# schematic.net
KiCad netlist of a schematic drawn in EAGLE
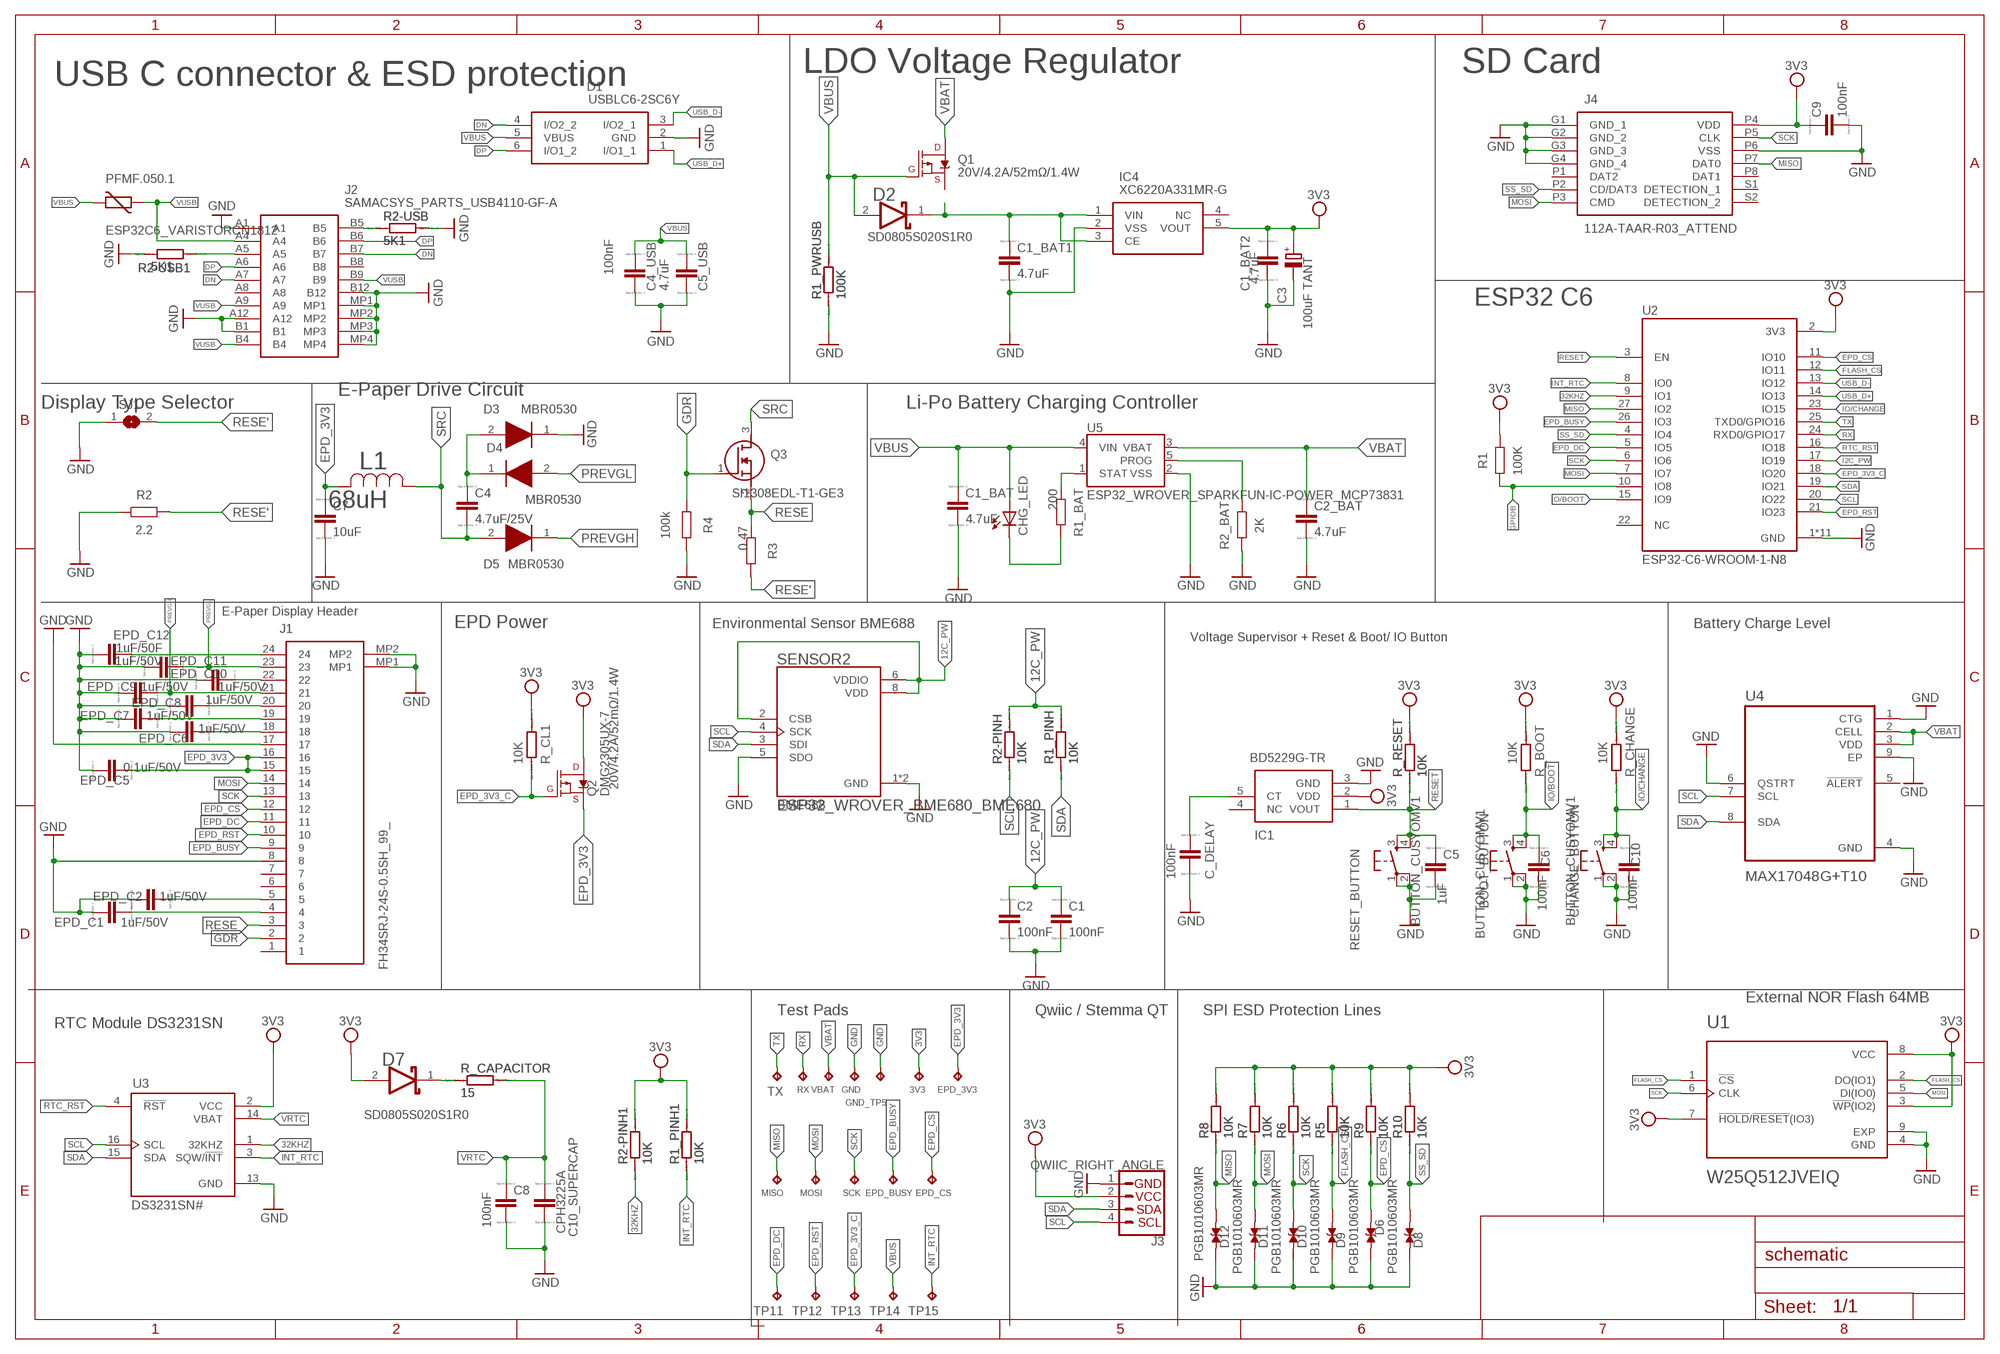
[diagram p0: schematic, sheet 1]

(export (version "E")
  (design (tool "Eeschema 10.0.6"))
  (components
    (comp (ref "3V3")
      (value "TPTP20R")
      (footprint "eagle-import:TP20R")
      (libsource (lib "eagle-import") (part "TPTP20R"))
    )
    (comp (ref "BOOT_BUTTON")
      (value "BUTTON_CUSYOMV1")
      (footprint "eagle-import:MYBUTTON")
      (libsource (lib "eagle-import") (part "BUTTON_CUSYOMV1"))
    )
    (comp (ref "C1")
      (value "100nF")
      (footprint "eagle-import:ESP32_WROVER_EAGLE-LTSPICE_C0402")
      (libsource (lib "eagle-import") (part "ESP32_WROVER_EAGLE-LTSPICE_CC0402"))
    )
    (comp (ref "C1_BAT")
      (value "4.7uF")
      (footprint "eagle-import:ESP32_WROVER_EAGLE-LTSPICE_C0402")
      (libsource (lib "eagle-import") (part "ESP32_WROVER_EAGLE-LTSPICE_CC0402"))
    )
    (comp (ref "C1_BAT1")
      (value "4.7uF")
      (footprint "eagle-import:ESP32_WROVER_EAGLE-LTSPICE_C0402")
      (libsource (lib "eagle-import") (part "ESP32_WROVER_EAGLE-LTSPICE_CC0402"))
    )
    (comp (ref "C1_BAT2")
      (value "4.7uF")
      (footprint "eagle-import:ESP32_WROVER_EAGLE-LTSPICE_C0402")
      (libsource (lib "eagle-import") (part "ESP32_WROVER_EAGLE-LTSPICE_CC0402"))
    )
    (comp (ref "C2")
      (value "100nF")
      (footprint "eagle-import:ESP32_WROVER_EAGLE-LTSPICE_C0402")
      (libsource (lib "eagle-import") (part "ESP32_WROVER_EAGLE-LTSPICE_CC0402"))
    )
    (comp (ref "C2_BAT")
      (value "4.7uF")
      (footprint "eagle-import:ESP32_WROVER_EAGLE-LTSPICE_C0402")
      (libsource (lib "eagle-import") (part "ESP32_WROVER_EAGLE-LTSPICE_CC0402"))
    )
    (comp (ref "C3")
      (value "100uF TANT")
      (footprint "eagle-import:RCL_CT3528")
      (libsource (lib "eagle-import") (part "RCL_CPOL-EUCT3528"))
    )
    (comp (ref "C4")
      (value "4.7uF/25V")
      (footprint "eagle-import:ESP32_WROVER_EAGLE-LTSPICE_C0402")
      (libsource (lib "eagle-import") (part "ESP32_WROVER_EAGLE-LTSPICE_CC0402"))
    )
    (comp (ref "C4_USB")
      (value "100nF")
      (footprint "eagle-import:ESP32_WROVER_EAGLE-LTSPICE_C0402")
      (libsource (lib "eagle-import") (part "ESP32_WROVER_EAGLE-LTSPICE_CC0402"))
    )
    (comp (ref "C5")
      (value "1uF")
      (footprint "eagle-import:EAGLE-LTSPICE_C0402")
      (libsource (lib "eagle-import") (part "EAGLE-LTSPICE_CC0402"))
    )
    (comp (ref "C5_USB")
      (value "4.7uF")
      (footprint "eagle-import:ESP32_WROVER_EAGLE-LTSPICE_C0402")
      (libsource (lib "eagle-import") (part "ESP32_WROVER_EAGLE-LTSPICE_CC0402"))
    )
    (comp (ref "C6")
      (value "100nF")
      (footprint "eagle-import:ESP32_WROVER_EAGLE-LTSPICE_C0402")
      (libsource (lib "eagle-import") (part "ESP32_WROVER_EAGLE-LTSPICE_CC0402"))
    )
    (comp (ref "C7")
      (value "10uF")
      (footprint "eagle-import:ESP32_WROVER_EAGLE-LTSPICE_C0402")
      (libsource (lib "eagle-import") (part "ESP32_WROVER_EAGLE-LTSPICE_CC0402"))
    )
    (comp (ref "C8")
      (value "100nF")
      (footprint "eagle-import:EAGLE-LTSPICE_C0402")
      (libsource (lib "eagle-import") (part "EAGLE-LTSPICE_CC0402"))
    )
    (comp (ref "C9")
      (value "100nF")
      (footprint "eagle-import:ESP32_WROVER_EAGLE-LTSPICE_C0402")
      (libsource (lib "eagle-import") (part "ESP32_WROVER_EAGLE-LTSPICE_CC0402"))
    )
    (comp (ref "C10")
      (value "100nF")
      (footprint "eagle-import:ESP32_WROVER_EAGLE-LTSPICE_C0402")
      (libsource (lib "eagle-import") (part "ESP32_WROVER_EAGLE-LTSPICE_CC0402"))
    )
    (comp (ref "C10_SUPERCAP")
      (value "CPH3225A")
      (footprint "eagle-import:EAGLE-LTSPICE_C0402")
      (libsource (lib "eagle-import") (part "EAGLE-LTSPICE_CC0402"))
    )
    (comp (ref "CHANGE_BUTTON")
      (value "BUTTON_CUSYOMV1")
      (footprint "eagle-import:MYBUTTON")
      (libsource (lib "eagle-import") (part "BUTTON_CUSYOMV1"))
    )
    (comp (ref "CHG_LED")
      (value "ADAFRUIT_LEDCHIP-LED0603")
      (footprint "eagle-import:ADAFRUIT_CHIP-LED0603")
      (libsource (lib "eagle-import") (part "ADAFRUIT_LEDCHIP-LED0603"))
    )
    (comp (ref "C_DELAY")
      (value "100nF")
      (footprint "eagle-import:ESP32_WROVER_EAGLE-LTSPICE_C0402")
      (libsource (lib "eagle-import") (part "ESP32_WROVER_EAGLE-LTSPICE_CC0402"))
    )
    (comp (ref "D1")
      (value "USBLC6-2SC6Y")
      (footprint "eagle-import:SOT95P280X145.0100-6N")
      (fields (field (name "MF") "STMicroelectronics"))
      (libsource (lib "eagle-import") (part "USBLC6-2SC6Y"))
    )
    (comp (ref "D2")
      (value "ESP32_WROVER_AVX---SD0805S020S1R0_AVX_SD0805S020S1R0_0_0AVX_SD0805S020S1R0_0_0")
      (footprint "eagle-import:ESP32_WROVER_AVX---SD0805S020S1R0_AVX_SD0805S020S1R0_0")
      (fields
        (field (name "DIGIKEY_PART_NUMBER") "478-7800-1-ND")
        (field (name "MF") "AVX")
        (field (name "MOUSER_PART_NUMBER") "581-SD0805S020S1R0")
      )
      (libsource (lib "eagle-import") (part "ESP32_WROVER_AVX---SD0805S020S1R0_AVX_SD0805S020S1R0_0_0AVX_SD0805S020S1R0_0_0"))
    )
    (comp (ref "D3")
      (value "MBR0530")
      (footprint "eagle-import:SOD3716X135.0100N")
      (fields (field (name "MF") "ON Semiconductor"))
      (libsource (lib "eagle-import") (part "MBR0530"))
    )
    (comp (ref "D4")
      (value "MBR0530")
      (footprint "eagle-import:SOD3716X135.0100N")
      (fields (field (name "MF") "ON Semiconductor"))
      (libsource (lib "eagle-import") (part "MBR0530"))
    )
    (comp (ref "D5")
      (value "MBR0530")
      (footprint "eagle-import:SOD3716X135.0100N")
      (fields (field (name "MF") "ON Semiconductor"))
      (libsource (lib "eagle-import") (part "MBR0530"))
    )
    (comp (ref "D6")
      (value "PGB1010603MR")
      (footprint "eagle-import:DIOC1608X36.0100N")
      (fields (field (name "MF") "Littelfuse Inc."))
      (libsource (lib "eagle-import") (part "PGB1010603MR"))
    )
    (comp (ref "D7")
      (value "ESP32_WROVER_AVX---SD0805S020S1R0_AVX_SD0805S020S1R0_0_0AVX_SD0805S020S1R0_0_0")
      (footprint "eagle-import:ESP32_WROVER_AVX---SD0805S020S1R0_AVX_SD0805S020S1R0_0")
      (fields
        (field (name "DIGIKEY_PART_NUMBER") "478-7800-1-ND")
        (field (name "MF") "AVX")
        (field (name "MOUSER_PART_NUMBER") "581-SD0805S020S1R0")
      )
      (libsource (lib "eagle-import") (part "ESP32_WROVER_AVX---SD0805S020S1R0_AVX_SD0805S020S1R0_0_0AVX_SD0805S020S1R0_0_0"))
    )
    (comp (ref "D8")
      (value "PGB1010603MR")
      (footprint "eagle-import:DIOC1608X36.0100N")
      (fields (field (name "MF") "Littelfuse Inc."))
      (libsource (lib "eagle-import") (part "PGB1010603MR"))
    )
    (comp (ref "D9")
      (value "PGB1010603MR")
      (footprint "eagle-import:DIOC1608X36.0100N")
      (fields (field (name "MF") "Littelfuse Inc."))
      (libsource (lib "eagle-import") (part "PGB1010603MR"))
    )
    (comp (ref "D10")
      (value "PGB1010603MR")
      (footprint "eagle-import:DIOC1608X36.0100N")
      (fields (field (name "MF") "Littelfuse Inc."))
      (libsource (lib "eagle-import") (part "PGB1010603MR"))
    )
    (comp (ref "D11")
      (value "PGB1010603MR")
      (footprint "eagle-import:DIOC1608X36.0100N")
      (fields (field (name "MF") "Littelfuse Inc."))
      (libsource (lib "eagle-import") (part "PGB1010603MR"))
    )
    (comp (ref "D12")
      (value "PGB1010603MR")
      (footprint "eagle-import:DIOC1608X36.0100N")
      (fields (field (name "MF") "Littelfuse Inc."))
      (libsource (lib "eagle-import") (part "PGB1010603MR"))
    )
    (comp (ref "EPD_3V3")
      (value "TPTP20R")
      (footprint "eagle-import:TP20R")
      (libsource (lib "eagle-import") (part "TPTP20R"))
    )
    (comp (ref "EPD_BUSY")
      (value "TPTP20R")
      (footprint "eagle-import:TP20R")
      (libsource (lib "eagle-import") (part "TPTP20R"))
    )
    (comp (ref "EPD_C1")
      (value "1uF/50V")
      (footprint "eagle-import:ESP32_WROVER_EAGLE-LTSPICE_C0402")
      (libsource (lib "eagle-import") (part "ESP32_WROVER_EAGLE-LTSPICE_CC0402"))
    )
    (comp (ref "EPD_C2")
      (value "1uF/50V")
      (footprint "eagle-import:ESP32_WROVER_EAGLE-LTSPICE_C0402")
      (libsource (lib "eagle-import") (part "ESP32_WROVER_EAGLE-LTSPICE_CC0402"))
    )
    (comp (ref "EPD_C5")
      (value "0.1uF/50V")
      (footprint "eagle-import:ESP32_WROVER_EAGLE-LTSPICE_C0402")
      (libsource (lib "eagle-import") (part "ESP32_WROVER_EAGLE-LTSPICE_CC0402"))
    )
    (comp (ref "EPD_C6")
      (value "1uF/50V")
      (footprint "eagle-import:ESP32_WROVER_EAGLE-LTSPICE_C0402")
      (libsource (lib "eagle-import") (part "ESP32_WROVER_EAGLE-LTSPICE_CC0402"))
    )
    (comp (ref "EPD_C7")
      (value "1uF/50V")
      (footprint "eagle-import:ESP32_WROVER_EAGLE-LTSPICE_C0402")
      (libsource (lib "eagle-import") (part "ESP32_WROVER_EAGLE-LTSPICE_CC0402"))
    )
    (comp (ref "EPD_C8")
      (value "1uF/50V")
      (footprint "eagle-import:ESP32_WROVER_EAGLE-LTSPICE_C0402")
      (libsource (lib "eagle-import") (part "ESP32_WROVER_EAGLE-LTSPICE_CC0402"))
    )
    (comp (ref "EPD_C9")
      (value "1uF/50V")
      (footprint "eagle-import:ESP32_WROVER_EAGLE-LTSPICE_C0402")
      (libsource (lib "eagle-import") (part "ESP32_WROVER_EAGLE-LTSPICE_CC0402"))
    )
    (comp (ref "EPD_C10")
      (value "1uF/50V")
      (footprint "eagle-import:ESP32_WROVER_EAGLE-LTSPICE_C0402")
      (libsource (lib "eagle-import") (part "ESP32_WROVER_EAGLE-LTSPICE_CC0402"))
    )
    (comp (ref "EPD_C11")
      (value "1uF/50V")
      (footprint "eagle-import:ESP32_WROVER_EAGLE-LTSPICE_C0402")
      (libsource (lib "eagle-import") (part "ESP32_WROVER_EAGLE-LTSPICE_CC0402"))
    )
    (comp (ref "EPD_C12")
      (value "1uF/50F")
      (footprint "eagle-import:ESP32_WROVER_EAGLE-LTSPICE_C0402")
      (libsource (lib "eagle-import") (part "ESP32_WROVER_EAGLE-LTSPICE_CC0402"))
    )
    (comp (ref "EPD_CS")
      (value "TPTP20R")
      (footprint "eagle-import:TP20R")
      (libsource (lib "eagle-import") (part "TPTP20R"))
    )
    (comp (ref "GND")
      (value "TPTP20R")
      (footprint "eagle-import:TP20R")
      (libsource (lib "eagle-import") (part "TPTP20R"))
    )
    (comp (ref "GND_TP5")
      (value "TPTP20R")
      (footprint "eagle-import:TP20R")
      (libsource (lib "eagle-import") (part "TPTP20R"))
    )
    (comp (ref "IC1")
      (value "BD5229G-TR")
      (footprint "eagle-import:SOT95P280X125.0100-5N")
      (fields (field (name "MOUSER_PART_NUMBER") "755-BD5229G-TR"))
      (libsource (lib "eagle-import") (part "BD5229G-TR"))
    )
    (comp (ref "IC4")
      (value "XC6220A331MR-G")
      (footprint "eagle-import:SOT95P280X120.0100-5N")
      (fields (field (name "MOUSER_PART_NUMBER") "865-XC6220A331MR-G"))
      (libsource (lib "eagle-import") (part "XC6220A331MR-G"))
    )
    (comp (ref "J1")
      (value "FH34SRJ-24S-0.5SH_99_")
      (footprint "eagle-import:FH34SRJ24S05SH99")
      (fields
        (field (name "MANUFACTURER_PART_NUMBER") "FH34SRJ-24S-0.5SH(99)")
        (field (name "MOUSER_PART_NUMBER") "798-FH34SRJ24S05SH99")
      )
      (libsource (lib "eagle-import") (part "FH34SRJ-24S-0.5SH_99_"))
    )
    (comp (ref "J2")
      (value "SAMACSYS_PARTS_USB4110-GF-A")
      (footprint "eagle-import:SAMACSYS_PARTS_USB4110GFA")
      (fields
        (field (name "MANUFACTURER_PART_NUMBER") "USB4110-GF-A")
        (field (name "MOUSER_PART_NUMBER") "640-USB4110-GF-A")
      )
      (libsource (lib "eagle-import") (part "SAMACSYS_PARTS_USB4110-GF-A"))
    )
    (comp (ref "J3")
      (value "QWIIC_RIGHT_ANGLE")
      (footprint "eagle-import:JST04_1MM_RA")
      (libsource (lib "eagle-import") (part "QWIIC_CONNECTORJS-1MM"))
    )
    (comp (ref "J4")
      (value "112A-TAAR-R03_ATTEND")
      (footprint "eagle-import:112ATAARR03ATTEND")
      (fields (field (name "MANUFACTURER_PART_NUMBER") "112A-TAAR-R03 ATTEND"))
      (libsource (lib "eagle-import") (part "112A-TAAR-R03_ATTEND"))
    )
    (comp (ref "L1")
      (value "68uH")
      (footprint "eagle-import:IND_4828-WE-TPC_WRE")
      (fields
        (field (name "MANUFACTURER_PART_NUMBER") "744043680")
        (field (name "COPYRIGHT") "Copyright (C) 2024 Ultra Librarian. All rights reserved.")
      )
      (libsource (lib "eagle-import") (part "744043680IND_4828-WE-TPC_WRE"))
    )
    (comp (ref "MISO")
      (value "TPTP20R")
      (footprint "eagle-import:TP20R")
      (libsource (lib "eagle-import") (part "TPTP20R"))
    )
    (comp (ref "MOSI")
      (value "TPTP20R")
      (footprint "eagle-import:TP20R")
      (libsource (lib "eagle-import") (part "TPTP20R"))
    )
    (comp (ref "PFMF.050.1")
      (value "ESP32C6_VARISTORCN1812")
      (footprint "eagle-import:ESP32C6_VARISTOR_CT_CN1812")
      (libsource (lib "eagle-import") (part "ESP32C6_VARISTORCN1812"))
    )
    (comp (ref "Q1")
      (value "20V/4.2A/52mΩ/1.4W")
      (footprint "eagle-import:ESP32_WROVER_SPARKFUN-DISCRETESEMI_SOT23-3")
      (libsource (lib "eagle-import") (part "ESP32_WROVER_SPARKFUN-DISCRETESEMI_MOSFET_PCH-DMG2305UX-7"))
    )
    (comp (ref "Q2")
      (value "20V/4.2A/52mΩ/1.4W")
      (footprint "eagle-import:ESP32_WROVER_SPARKFUN-DISCRETESEMI_SOT23-3")
      (libsource (lib "eagle-import") (part "ESP32_WROVER_SPARKFUN-DISCRETESEMI_MOSFET_PCH-DMG2305UX-7"))
    )
    (comp (ref "Q3")
      (value "SI1308EDL-T1-GE3")
      (footprint "eagle-import:SOT65P210X110.0100-3N")
      (fields (field (name "MF") "Vishay Siliconix"))
      (libsource (lib "eagle-import") (part "SI1308EDL-T1-GE3"))
    )
    (comp (ref "R1")
      (value "100K")
      (footprint "eagle-import:RESC1005X40.0100")
      (libsource (lib "eagle-import") (part "RCHIP-0402(1005-METRIC)_"))
    )
    (comp (ref "R1_BAT")
      (value "200")
      (footprint "eagle-import:RESC1005X40.0100")
      (libsource (lib "eagle-import") (part "RCHIP-0402(1005-METRIC)_"))
    )
    (comp (ref "R1_PINH")
      (value "10K")
      (footprint "eagle-import:ESP32_WROVER_EAGLE-LTSPICE_R0402")
      (libsource (lib "eagle-import") (part "ESP32_WROVER_EAGLE-LTSPICE_RR0402"))
    )
    (comp (ref "R1_PINH1")
      (value "10K")
      (footprint "eagle-import:ESP32_WROVER_EAGLE-LTSPICE_R0402")
      (libsource (lib "eagle-import") (part "ESP32_WROVER_EAGLE-LTSPICE_RR0402"))
    )
    (comp (ref "R1_PWRUSB")
      (value "100K")
      (footprint "eagle-import:ESP32_WROVER_EAGLE-LTSPICE_R0402")
      (libsource (lib "eagle-import") (part "ESP32_WROVER_EAGLE-LTSPICE_RR0402"))
    )
    (comp (ref "R2")
      (value "2.2")
      (footprint "eagle-import:RESC1005X40.0100")
      (libsource (lib "eagle-import") (part "RCHIP-0402(1005-METRIC)_"))
    )
    (comp (ref "R2-PINH")
      (value "10K")
      (footprint "eagle-import:ESP32_WROVER_EAGLE-LTSPICE_R0402")
      (libsource (lib "eagle-import") (part "ESP32_WROVER_EAGLE-LTSPICE_RR0402"))
    )
    (comp (ref "R2-PINH1")
      (value "10K")
      (footprint "eagle-import:ESP32_WROVER_EAGLE-LTSPICE_R0402")
      (libsource (lib "eagle-import") (part "ESP32_WROVER_EAGLE-LTSPICE_RR0402"))
    )
    (comp (ref "R2-USB")
      (value "5K1")
      (footprint "eagle-import:ESP32_WROVER_EAGLE-LTSPICE_R0402")
      (libsource (lib "eagle-import") (part "ESP32_WROVER_EAGLE-LTSPICE_RR0402"))
    )
    (comp (ref "R2-USB1")
      (value "5K1")
      (footprint "eagle-import:ESP32_WROVER_EAGLE-LTSPICE_R0402")
      (libsource (lib "eagle-import") (part "ESP32_WROVER_EAGLE-LTSPICE_RR0402"))
    )
    (comp (ref "R2_BAT")
      (value "2K")
      (footprint "eagle-import:RESC1005X40.0100")
      (libsource (lib "eagle-import") (part "RCHIP-0402(1005-METRIC)_"))
    )
    (comp (ref "R3")
      (value "0.47")
      (footprint "eagle-import:RESC1005X40.0100")
      (libsource (lib "eagle-import") (part "RCHIP-0402(1005-METRIC)_"))
    )
    (comp (ref "R4")
      (value "100k")
      (footprint "eagle-import:RESC1005X40.0100")
      (libsource (lib "eagle-import") (part "RCHIP-0402(1005-METRIC)_"))
    )
    (comp (ref "R5")
      (value "10K")
      (footprint "eagle-import:ESP32_WROVER_EAGLE-LTSPICE_R0402")
      (libsource (lib "eagle-import") (part "ESP32_WROVER_EAGLE-LTSPICE_RR0402"))
    )
    (comp (ref "R6")
      (value "10K")
      (footprint "eagle-import:ESP32_WROVER_EAGLE-LTSPICE_R0402")
      (libsource (lib "eagle-import") (part "ESP32_WROVER_EAGLE-LTSPICE_RR0402"))
    )
    (comp (ref "R7")
      (value "10K")
      (footprint "eagle-import:ESP32_WROVER_EAGLE-LTSPICE_R0402")
      (libsource (lib "eagle-import") (part "ESP32_WROVER_EAGLE-LTSPICE_RR0402"))
    )
    (comp (ref "R8")
      (value "10K")
      (footprint "eagle-import:ESP32_WROVER_EAGLE-LTSPICE_R0402")
      (libsource (lib "eagle-import") (part "ESP32_WROVER_EAGLE-LTSPICE_RR0402"))
    )
    (comp (ref "R9")
      (value "10K")
      (footprint "eagle-import:ESP32_WROVER_EAGLE-LTSPICE_R0402")
      (libsource (lib "eagle-import") (part "ESP32_WROVER_EAGLE-LTSPICE_RR0402"))
    )
    (comp (ref "R10")
      (value "10K")
      (footprint "eagle-import:ESP32_WROVER_EAGLE-LTSPICE_R0402")
      (libsource (lib "eagle-import") (part "ESP32_WROVER_EAGLE-LTSPICE_RR0402"))
    )
    (comp (ref "RESET_BUTTON")
      (value "BUTTON_CUSYOMV1")
      (footprint "eagle-import:MYBUTTON")
      (libsource (lib "eagle-import") (part "BUTTON_CUSYOMV1"))
    )
    (comp (ref "RX")
      (value "TPTP20R")
      (footprint "eagle-import:TP20R")
      (libsource (lib "eagle-import") (part "TPTP20R"))
    )
    (comp (ref "R_BOOT")
      (value "10K")
      (footprint "eagle-import:ESP32_WROVER_EAGLE-LTSPICE_R0402")
      (libsource (lib "eagle-import") (part "ESP32_WROVER_EAGLE-LTSPICE_RR0402"))
    )
    (comp (ref "R_CAPACITOR")
      (value "15")
      (footprint "eagle-import:ESP32_WROVER_EAGLE-LTSPICE_R0402")
      (libsource (lib "eagle-import") (part "ESP32_WROVER_EAGLE-LTSPICE_RR0402"))
    )
    (comp (ref "R_CHANGE")
      (value "10K")
      (footprint "eagle-import:ESP32_WROVER_EAGLE-LTSPICE_R0402")
      (libsource (lib "eagle-import") (part "ESP32_WROVER_EAGLE-LTSPICE_RR0402"))
    )
    (comp (ref "R_CL1")
      (value "10K")
      (footprint "eagle-import:ESP32_WROVER_EAGLE-LTSPICE_R0402")
      (libsource (lib "eagle-import") (part "ESP32_WROVER_EAGLE-LTSPICE_RR0402"))
    )
    (comp (ref "R_RESET")
      (value "10K")
      (footprint "eagle-import:ESP32_WROVER_EAGLE-LTSPICE_R0402")
      (libsource (lib "eagle-import") (part "ESP32_WROVER_EAGLE-LTSPICE_RR0402"))
    )
    (comp (ref "SCK")
      (value "TPTP20R")
      (footprint "eagle-import:TP20R")
      (libsource (lib "eagle-import") (part "TPTP20R"))
    )
    (comp (ref "SENSOR2")
      (value "ESP32_WROVER_BME680_BME680")
      (footprint "eagle-import:ESP32_WROVER_BME680_PSON80P300X300.0100X100-8N")
      (fields (field (name "MF") "Bosch Sensortec") (field (name "MP") "BME680"))
      (libsource (lib "eagle-import") (part "ESP32_WROVER_BME680_BME680"))
    )
    (comp (ref "SJ1") (value "SJ") (footprint "eagle-import:SJ") (libsource (lib "eagle-import") (part "SJ")))
    (comp (ref "TP11")
      (value "TPTP20R")
      (footprint "eagle-import:TP20R")
      (libsource (lib "eagle-import") (part "TPTP20R"))
    )
    (comp (ref "TP12")
      (value "TPTP20R")
      (footprint "eagle-import:TP20R")
      (libsource (lib "eagle-import") (part "TPTP20R"))
    )
    (comp (ref "TP13")
      (value "TPTP20R")
      (footprint "eagle-import:TP20R")
      (libsource (lib "eagle-import") (part "TPTP20R"))
    )
    (comp (ref "TP14")
      (value "TPTP20R")
      (footprint "eagle-import:TP20R")
      (libsource (lib "eagle-import") (part "TPTP20R"))
    )
    (comp (ref "TP15")
      (value "TPTP20R")
      (footprint "eagle-import:TP20R")
      (libsource (lib "eagle-import") (part "TPTP20R"))
    )
    (comp (ref "TX")
      (value "TPTP20R")
      (footprint "eagle-import:TP20R")
      (libsource (lib "eagle-import") (part "TPTP20R"))
    )
    (comp (ref "U1")
      (value "W25Q512JVEIQ")
      (footprint "eagle-import:SON127P600X800.0100X80-9N")
      (fields (field (name "MF") "Winbond Electronics"))
      (libsource (lib "eagle-import") (part "W25Q512JVEIQ"))
    )
    (comp (ref "U2")
      (value "ESP32-C6-WROOM-1-N8")
      (footprint "eagle-import:XCVR_ESP32-C6-WROOM-1-N8")
      (fields (field (name "MF") "Espressif Systems"))
      (libsource (lib "eagle-import") (part "ESP32-C6-WROOM-1-N8"))
    )
    (comp (ref "U3")
      (value "DS3231SN#")
      (footprint "eagle-import:SOIC127P1032X265.0100-16N")
      (fields (field (name "MF") "Analog Devices"))
      (libsource (lib "eagle-import") (part "DS3231SN#"))
    )
    (comp (ref "U4")
      (value "MAX17048G+T10")
      (footprint "eagle-import:SON50P200X200.0100X80-9N")
      (fields (field (name "MF") "Analog Devices") (field (name "MP") "MAX17048.0100G+T10"))
      (libsource (lib "eagle-import") (part "MAX17048.0100G+T10"))
    )
    (comp (ref "U5")
      (value "ESP32_WROVER_SPARKFUN-IC-POWER_MCP73831")
      (footprint "eagle-import:ESP32_WROVER_SPARKFUN-IC-POWER_SOT23-5")
      (libsource (lib "eagle-import") (part "ESP32_WROVER_SPARKFUN-IC-POWER_MCP73831"))
    )
    (comp (ref "VBAT")
      (value "TPTP20R")
      (footprint "eagle-import:TP20R")
      (libsource (lib "eagle-import") (part "TPTP20R"))
    )
  )
  (nets
    (net (code "1") (name "3V3") (class "Default")
      (node (ref "3V3") (pin "TP") (pinfunction "TP_TP") (pintype "input"))
      (node (ref "C1_BAT2") (pin "1") (pinfunction "1_1") (pintype "passive"))
      (node (ref "C3") (pin "+") (pinfunction "+_+") (pintype "passive"))
      (node (ref "C9") (pin "1") (pinfunction "1_1") (pintype "passive"))
      (node (ref "D7") (pin "2") (pinfunction "ANODE_2") (pintype "bidirectional"))
      (node (ref "IC1") (pin "2") (pinfunction "VDD_2") (pintype "bidirectional"))
      (node (ref "IC4") (pin "5") (pinfunction "VOUT_5") (pintype "bidirectional"))
      (node (ref "J3") (pin "2") (pinfunction "2_2") (pintype "power_in"))
      (node (ref "J4") (pin "P4") (pinfunction "VDD_P4") (pintype "bidirectional"))
      (node (ref "Q2") (pin "3") (pinfunction "D_3") (pintype "bidirectional"))
      (node (ref "R1") (pin "2") (pinfunction "2_2") (pintype "passive"))
      (node (ref "R10") (pin "2") (pinfunction "2_2") (pintype "passive"))
      (node (ref "R1_PINH1") (pin "2") (pinfunction "2_2") (pintype "passive"))
      (node (ref "R2-PINH1") (pin "2") (pinfunction "2_2") (pintype "passive"))
      (node (ref "R5") (pin "2") (pinfunction "2_2") (pintype "passive"))
      (node (ref "R6") (pin "2") (pinfunction "2_2") (pintype "passive"))
      (node (ref "R7") (pin "2") (pinfunction "2_2") (pintype "passive"))
      (node (ref "R8") (pin "2") (pinfunction "2_2") (pintype "passive"))
      (node (ref "R9") (pin "2") (pinfunction "2_2") (pintype "passive"))
      (node (ref "R_BOOT") (pin "2") (pinfunction "2_2") (pintype "passive"))
      (node (ref "R_CHANGE") (pin "2") (pinfunction "2_2") (pintype "passive"))
      (node (ref "R_CL1") (pin "2") (pinfunction "2_2") (pintype "passive"))
      (node (ref "R_RESET") (pin "2") (pinfunction "2_2") (pintype "passive"))
      (node (ref "U1") (pin "3") (pinfunction "~{WP}(IO2)_3") (pintype "bidirectional"))
      (node (ref "U1") (pin "7") (pinfunction "~{HOLD}/~{RESET}(IO3)_7") (pintype "bidirectional"))
      (node (ref "U1") (pin "8") (pinfunction "VCC_8") (pintype "power_in"))
      (node (ref "U2") (pin "2") (pinfunction "3V3_2") (pintype "power_in"))
      (node (ref "U3") (pin "2") (pinfunction "VCC_2") (pintype "power_in"))
    )
    (net (code "2") (name "12C_PW") (class "Default")
      (node (ref "C1") (pin "1") (pinfunction "1_1") (pintype "passive"))
      (node (ref "C2") (pin "1") (pinfunction "1_1") (pintype "passive"))
      (node (ref "R1_PINH") (pin "2") (pinfunction "2_2") (pintype "passive"))
      (node (ref "R2-PINH") (pin "2") (pinfunction "2_2") (pintype "passive"))
      (node (ref "SENSOR2") (pin "2") (pinfunction "CSB_2") (pintype "input"))
      (node (ref "SENSOR2") (pin "6") (pinfunction "VDDIO_6") (pintype "power_in"))
      (node (ref "SENSOR2") (pin "8") (pinfunction "VDD_8") (pintype "power_in"))
    )
    (net (code "3") (name "32KHZ") (class "Default")
      (node (ref "R2-PINH1") (pin "1") (pinfunction "1_1") (pintype "passive"))
      (node (ref "U2") (pin "9") (pinfunction "IO1_9") (pintype "bidirectional"))
      (node (ref "U3") (pin "1") (pinfunction "32KHZ_1") (pintype "output"))
    )
    (net (code "4") (name "DN") (class "Default")
      (node (ref "D1") (pin "4") (pinfunction "I/O2_2_4") (pintype "bidirectional"))
      (node (ref "J2") (pin "A7") (pinfunction "A7_A7") (pintype "bidirectional"))
      (node (ref "J2") (pin "B7") (pinfunction "B7_B7") (pintype "bidirectional"))
    )
    (net (code "5") (name "DP") (class "Default")
      (node (ref "D1") (pin "6") (pinfunction "I/O1_2_6") (pintype "bidirectional"))
      (node (ref "J2") (pin "A6") (pinfunction "A6_A6") (pintype "bidirectional"))
      (node (ref "J2") (pin "B6") (pinfunction "B6_B6") (pintype "bidirectional"))
    )
    (net (code "6") (name "EPD_3V3") (class "Default")
      (node (ref "C7") (pin "1") (pinfunction "1_1") (pintype "passive"))
      (node (ref "EPD_3V3") (pin "TP") (pinfunction "TP_TP") (pintype "input"))
      (node (ref "EPD_C5") (pin "2") (pinfunction "2_2") (pintype "passive"))
      (node (ref "J1") (pin "15") (pinfunction "15_15") (pintype "bidirectional"))
      (node (ref "J1") (pin "16") (pinfunction "16_16") (pintype "bidirectional"))
      (node (ref "L1") (pin "2") (pinfunction "2_2") (pintype "passive"))
      (node (ref "Q2") (pin "2") (pinfunction "S_2") (pintype "bidirectional"))
    )
    (net (code "7") (name "EPD_3V3_C") (class "Default")
      (node (ref "Q2") (pin "1") (pinfunction "G_1") (pintype "bidirectional"))
      (node (ref "R_CL1") (pin "1") (pinfunction "1_1") (pintype "passive"))
      (node (ref "TP13") (pin "TP") (pinfunction "TP_TP") (pintype "input"))
      (node (ref "U2") (pin "18") (pinfunction "IO20_18") (pintype "bidirectional"))
    )
    (net (code "8") (name "EPD_BUSY") (class "Default")
      (node (ref "EPD_BUSY") (pin "TP") (pinfunction "TP_TP") (pintype "input"))
      (node (ref "J1") (pin "9") (pinfunction "9_9") (pintype "bidirectional"))
      (node (ref "U2") (pin "26") (pinfunction "IO3_26") (pintype "bidirectional"))
    )
    (net (code "9") (name "EPD_CS") (class "Default")
      (node (ref "D6") (pin "2") (pinfunction "2_2") (pintype "passive"))
      (node (ref "EPD_CS") (pin "TP") (pinfunction "TP_TP") (pintype "input"))
      (node (ref "J1") (pin "12") (pinfunction "12_12") (pintype "bidirectional"))
      (node (ref "R9") (pin "1") (pinfunction "1_1") (pintype "passive"))
      (node (ref "U2") (pin "11") (pinfunction "IO10_11") (pintype "bidirectional"))
    )
    (net (code "10") (name "EPD_DC") (class "Default")
      (node (ref "J1") (pin "11") (pinfunction "11_11") (pintype "bidirectional"))
      (node (ref "TP11") (pin "TP") (pinfunction "TP_TP") (pintype "input"))
      (node (ref "U2") (pin "5") (pinfunction "IO5_5") (pintype "bidirectional"))
    )
    (net (code "11") (name "EPD_RST") (class "Default")
      (node (ref "J1") (pin "10") (pinfunction "10_10") (pintype "bidirectional"))
      (node (ref "TP12") (pin "TP") (pinfunction "TP_TP") (pintype "input"))
      (node (ref "U2") (pin "21") (pinfunction "IO23_21") (pintype "bidirectional"))
    )
    (net (code "12") (name "FLASH_CS") (class "Default")
      (node (ref "D9") (pin "2") (pinfunction "2_2") (pintype "passive"))
      (node (ref "R5") (pin "1") (pinfunction "1_1") (pintype "passive"))
      (node (ref "U1") (pin "1") (pinfunction "~{CS}_1") (pintype "input"))
      (node (ref "U2") (pin "12") (pinfunction "IO11_12") (pintype "bidirectional"))
    )
    (net (code "13") (name "GDR") (class "Default")
      (node (ref "J1") (pin "2") (pinfunction "2_2") (pintype "bidirectional"))
      (node (ref "Q3") (pin "1") (pinfunction "G_1") (pintype "bidirectional"))
      (node (ref "R4") (pin "2") (pinfunction "2_2") (pintype "passive"))
    )
    (net (code "14") (name "GND") (class "Default")
      (node (ref "BOOT_BUTTON") (pin "1") (pinfunction "1_1") (pintype "passive"))
      (node (ref "BOOT_BUTTON") (pin "2") (pinfunction "2_2") (pintype "passive"))
      (node (ref "C1") (pin "2") (pinfunction "2_2") (pintype "passive"))
      (node (ref "C10") (pin "2") (pinfunction "2_2") (pintype "passive"))
      (node (ref "C10_SUPERCAP") (pin "2") (pinfunction "2_2") (pintype "passive"))
      (node (ref "C1_BAT") (pin "2") (pinfunction "2_2") (pintype "passive"))
      (node (ref "C1_BAT1") (pin "2") (pinfunction "2_2") (pintype "passive"))
      (node (ref "C1_BAT2") (pin "2") (pinfunction "2_2") (pintype "passive"))
      (node (ref "C2") (pin "2") (pinfunction "2_2") (pintype "passive"))
      (node (ref "C2_BAT") (pin "2") (pinfunction "2_2") (pintype "passive"))
      (node (ref "C3") (pin "-") (pinfunction "-_-") (pintype "passive"))
      (node (ref "C4_USB") (pin "2") (pinfunction "2_2") (pintype "passive"))
      (node (ref "C5") (pin "2") (pinfunction "2_2") (pintype "passive"))
      (node (ref "C5_USB") (pin "2") (pinfunction "2_2") (pintype "passive"))
      (node (ref "C6") (pin "2") (pinfunction "2_2") (pintype "passive"))
      (node (ref "C7") (pin "2") (pinfunction "2_2") (pintype "passive"))
      (node (ref "C8") (pin "2") (pinfunction "2_2") (pintype "passive"))
      (node (ref "C9") (pin "2") (pinfunction "2_2") (pintype "passive"))
      (node (ref "CHANGE_BUTTON") (pin "1") (pinfunction "1_1") (pintype "passive"))
      (node (ref "CHANGE_BUTTON") (pin "2") (pinfunction "2_2") (pintype "passive"))
      (node (ref "C_DELAY") (pin "2") (pinfunction "2_2") (pintype "passive"))
      (node (ref "D1") (pin "2") (pinfunction "GND_2") (pintype "bidirectional"))
      (node (ref "D10") (pin "1") (pinfunction "1_1") (pintype "passive"))
      (node (ref "D11") (pin "1") (pinfunction "1_1") (pintype "passive"))
      (node (ref "D12") (pin "1") (pinfunction "1_1") (pintype "passive"))
      (node (ref "D3") (pin "1") (pinfunction "K_1") (pintype "bidirectional"))
      (node (ref "D6") (pin "1") (pinfunction "1_1") (pintype "passive"))
      (node (ref "D8") (pin "1") (pinfunction "1_1") (pintype "passive"))
      (node (ref "D9") (pin "1") (pinfunction "1_1") (pintype "passive"))
      (node (ref "EPD_C1") (pin "1") (pinfunction "1_1") (pintype "passive"))
      (node (ref "EPD_C10") (pin "1") (pinfunction "1_1") (pintype "passive"))
      (node (ref "EPD_C11") (pin "1") (pinfunction "1_1") (pintype "passive"))
      (node (ref "EPD_C12") (pin "1") (pinfunction "1_1") (pintype "passive"))
      (node (ref "EPD_C2") (pin "1") (pinfunction "1_1") (pintype "passive"))
      (node (ref "EPD_C5") (pin "1") (pinfunction "1_1") (pintype "passive"))
      (node (ref "EPD_C6") (pin "1") (pinfunction "1_1") (pintype "passive"))
      (node (ref "EPD_C7") (pin "1") (pinfunction "1_1") (pintype "passive"))
      (node (ref "EPD_C8") (pin "1") (pinfunction "1_1") (pintype "passive"))
      (node (ref "EPD_C9") (pin "1") (pinfunction "1_1") (pintype "passive"))
      (node (ref "GND") (pin "TP") (pinfunction "TP_TP") (pintype "input"))
      (node (ref "GND_TP5") (pin "TP") (pinfunction "TP_TP") (pintype "input"))
      (node (ref "IC1") (pin "3") (pinfunction "GND_3") (pintype "bidirectional"))
      (node (ref "IC4") (pin "2") (pinfunction "VSS_2") (pintype "bidirectional"))
      (node (ref "J1") (pin "17") (pinfunction "17_17") (pintype "bidirectional"))
      (node (ref "J1") (pin "8") (pinfunction "8_8") (pintype "bidirectional"))
      (node (ref "J1") (pin "MP1") (pinfunction "MP1_MP1") (pintype "bidirectional"))
      (node (ref "J1") (pin "MP2") (pinfunction "MP2_MP2") (pintype "bidirectional"))
      (node (ref "J2") (pin "A1") (pinfunction "A1_A1") (pintype "bidirectional"))
      (node (ref "J2") (pin "A12") (pinfunction "A12_A12") (pintype "bidirectional"))
      (node (ref "J2") (pin "B1") (pinfunction "B1_B1") (pintype "bidirectional"))
      (node (ref "J2") (pin "B12") (pinfunction "B12_B12") (pintype "bidirectional"))
      (node (ref "J2") (pin "MP1") (pinfunction "MP1_MP1") (pintype "bidirectional"))
      (node (ref "J2") (pin "MP2") (pinfunction "MP2_MP2") (pintype "bidirectional"))
      (node (ref "J2") (pin "MP3") (pinfunction "MP3_MP3") (pintype "bidirectional"))
      (node (ref "J2") (pin "MP4") (pinfunction "MP4_MP4") (pintype "bidirectional"))
      (node (ref "J3") (pin "1") (pinfunction "1_1") (pintype "power_in"))
      (node (ref "J4") (pin "G1") (pinfunction "GND_1_G1") (pintype "bidirectional"))
      (node (ref "J4") (pin "G2") (pinfunction "GND_2_G2") (pintype "bidirectional"))
      (node (ref "J4") (pin "G3") (pinfunction "GND_3_G3") (pintype "bidirectional"))
      (node (ref "J4") (pin "G4") (pinfunction "GND_4_G4") (pintype "bidirectional"))
      (node (ref "J4") (pin "P6") (pinfunction "VSS_P6") (pintype "bidirectional"))
      (node (ref "R1_PWRUSB") (pin "1") (pinfunction "1_1") (pintype "passive"))
      (node (ref "R2") (pin "1") (pinfunction "1_1") (pintype "passive"))
      (node (ref "R2-USB") (pin "2") (pinfunction "2_2") (pintype "passive"))
      (node (ref "R2-USB1") (pin "1") (pinfunction "1_1") (pintype "passive"))
      (node (ref "R2_BAT") (pin "1") (pinfunction "1_1") (pintype "passive"))
      (node (ref "R4") (pin "1") (pinfunction "1_1") (pintype "passive"))
      (node (ref "RESET_BUTTON") (pin "1") (pinfunction "1_1") (pintype "passive"))
      (node (ref "RESET_BUTTON") (pin "2") (pinfunction "2_2") (pintype "passive"))
      (node (ref "SENSOR2") (pin "1") (pinfunction "GND_1") (pintype "power_in"))
      (node (ref "SENSOR2") (pin "5") (pinfunction "SDO_5") (pintype "bidirectional"))
      (node (ref "SENSOR2") (pin "7") (pinfunction "GND_7") (pintype "power_in"))
      (node (ref "SJ1") (pin "1") (pinfunction "1_1") (pintype "passive"))
      (node (ref "U1") (pin "4") (pinfunction "GND_4") (pintype "power_in"))
      (node (ref "U1") (pin "9") (pinfunction "EXP_9") (pintype "passive"))
      (node (ref "U2") (pin "1") (pinfunction "GND_1") (pintype "power_in"))
      (node (ref "U2") (pin "28") (pinfunction "GND_28") (pintype "power_in"))
      (node (ref "U2") (pin "29_1") (pinfunction "GND_29_1") (pintype "power_in"))
      (node (ref "U2") (pin "29_2") (pinfunction "GND_29_2") (pintype "power_in"))
      (node (ref "U2") (pin "29_3") (pinfunction "GND_29_3") (pintype "power_in"))
      (node (ref "U2") (pin "29_4") (pinfunction "GND_29_4") (pintype "power_in"))
      (node (ref "U2") (pin "29_5") (pinfunction "GND_29_5") (pintype "power_in"))
      (node (ref "U2") (pin "29_6") (pinfunction "GND_29_6") (pintype "power_in"))
      (node (ref "U2") (pin "29_7") (pinfunction "GND_29_7") (pintype "power_in"))
      (node (ref "U2") (pin "29_8") (pinfunction "GND_29_8") (pintype "power_in"))
      (node (ref "U2") (pin "29_9") (pinfunction "GND_29_9") (pintype "power_in"))
      (node (ref "U3") (pin "13") (pinfunction "GND_13") (pintype "power_in"))
      (node (ref "U4") (pin "1") (pinfunction "CTG_1") (pintype "power_in"))
      (node (ref "U4") (pin "4") (pinfunction "GND_4") (pintype "power_in"))
      (node (ref "U4") (pin "6") (pinfunction "QSTRT_6") (pintype "input"))
      (node (ref "U4") (pin "9") (pinfunction "EP_9") (pintype "power_in"))
      (node (ref "U5") (pin "2") (pinfunction "VSS_2") (pintype "power_in"))
    )
    (net (code "15") (name "GPIOB") (class "Default")
      (node (ref "R1") (pin "1") (pinfunction "1_1") (pintype "passive"))
      (node (ref "U2") (pin "10") (pinfunction "IO8_10") (pintype "bidirectional"))
    )
    (net (code "16") (name "I2C_PW") (class "Default")
      (node (ref "U2") (pin "17") (pinfunction "IO19_17") (pintype "bidirectional"))
    )
    (net (code "17") (name "INT_RTC") (class "Default")
      (node (ref "R1_PINH1") (pin "1") (pinfunction "1_1") (pintype "passive"))
      (node (ref "TP15") (pin "TP") (pinfunction "TP_TP") (pintype "input"))
      (node (ref "U2") (pin "8") (pinfunction "IO0_8") (pintype "bidirectional"))
      (node (ref "U3") (pin "3") (pinfunction "SQW/~{INT}_3") (pintype "output"))
    )
    (net (code "18") (name "IO{slash}BOOT") (class "Default")
      (node (ref "BOOT_BUTTON") (pin "3") (pinfunction "3_3") (pintype "passive"))
      (node (ref "BOOT_BUTTON") (pin "4") (pinfunction "4_4") (pintype "passive"))
      (node (ref "C6") (pin "1") (pinfunction "1_1") (pintype "passive"))
      (node (ref "R_BOOT") (pin "1") (pinfunction "1_1") (pintype "passive"))
      (node (ref "U2") (pin "15") (pinfunction "IO9_15") (pintype "bidirectional"))
    )
    (net (code "19") (name "IO{slash}CHANGE") (class "Default")
      (node (ref "C10") (pin "1") (pinfunction "1_1") (pintype "passive"))
      (node (ref "CHANGE_BUTTON") (pin "3") (pinfunction "3_3") (pintype "passive"))
      (node (ref "CHANGE_BUTTON") (pin "4") (pinfunction "4_4") (pintype "passive"))
      (node (ref "R_CHANGE") (pin "1") (pinfunction "1_1") (pintype "passive"))
      (node (ref "U2") (pin "23") (pinfunction "IO15_23") (pintype "bidirectional"))
    )
    (net (code "20") (name "MISO") (class "Default")
      (node (ref "D12") (pin "2") (pinfunction "2_2") (pintype "passive"))
      (node (ref "J4") (pin "P7") (pinfunction "DAT0_P7") (pintype "bidirectional"))
      (node (ref "MISO") (pin "TP") (pinfunction "TP_TP") (pintype "input"))
      (node (ref "R8") (pin "1") (pinfunction "1_1") (pintype "passive"))
      (node (ref "U2") (pin "27") (pinfunction "IO2_27") (pintype "bidirectional"))
    )
    (net (code "21") (name "MOSI") (class "Default")
      (node (ref "D11") (pin "2") (pinfunction "2_2") (pintype "passive"))
      (node (ref "J1") (pin "14") (pinfunction "14_14") (pintype "bidirectional"))
      (node (ref "J4") (pin "P3") (pinfunction "CMD_P3") (pintype "bidirectional"))
      (node (ref "MOSI") (pin "TP") (pinfunction "TP_TP") (pintype "input"))
      (node (ref "R7") (pin "1") (pinfunction "1_1") (pintype "passive"))
      (node (ref "U1") (pin "5") (pinfunction "DI(IO0)_5") (pintype "bidirectional"))
      (node (ref "U2") (pin "7") (pinfunction "IO7_7") (pintype "bidirectional"))
    )
    (net (code "22") (name "Net-(CHG_LED-PadC)") (class "Default")
      (node (ref "CHG_LED") (pin "C") (pinfunction "C_C") (pintype "passive"))
      (node (ref "R1_BAT") (pin "1") (pinfunction "1_1") (pintype "passive"))
    )
    (net (code "23") (name "Net-(D2-CATHODE)") (class "Default")
      (node (ref "C1_BAT1") (pin "1") (pinfunction "1_1") (pintype "passive"))
      (node (ref "D2") (pin "1") (pinfunction "CATHODE_1") (pintype "bidirectional"))
      (node (ref "IC4") (pin "1") (pinfunction "VIN_1") (pintype "bidirectional"))
      (node (ref "IC4") (pin "3") (pinfunction "CE_3") (pintype "bidirectional"))
    )
    (net (code "24") (name "Net-(D3-A)") (class "Default")
      (node (ref "C4") (pin "1") (pinfunction "1_1") (pintype "passive"))
      (node (ref "D3") (pin "2") (pinfunction "A_2") (pintype "bidirectional"))
      (node (ref "D4") (pin "1") (pinfunction "K_1") (pintype "bidirectional"))
    )
    (net (code "25") (name "Net-(D7-CATHODE)") (class "Default")
      (node (ref "D7") (pin "1") (pinfunction "CATHODE_1") (pintype "bidirectional"))
      (node (ref "R_CAPACITOR") (pin "1") (pinfunction "1_1") (pintype "passive"))
    )
    (net (code "26") (name "Net-(EPD_C1-Pad2)") (class "Default")
      (node (ref "EPD_C1") (pin "2") (pinfunction "2_2") (pintype "passive"))
      (node (ref "J1") (pin "4") (pinfunction "4_4") (pintype "bidirectional"))
    )
    (net (code "27") (name "Net-(EPD_C2-Pad2)") (class "Default")
      (node (ref "EPD_C2") (pin "2") (pinfunction "2_2") (pintype "passive"))
      (node (ref "J1") (pin "5") (pinfunction "5_5") (pintype "bidirectional"))
    )
    (net (code "28") (name "Net-(EPD_C6-Pad2)") (class "Default")
      (node (ref "EPD_C6") (pin "2") (pinfunction "2_2") (pintype "passive"))
      (node (ref "J1") (pin "18") (pinfunction "18_18") (pintype "bidirectional"))
    )
    (net (code "29") (name "Net-(EPD_C7-Pad2)") (class "Default")
      (node (ref "EPD_C7") (pin "2") (pinfunction "2_2") (pintype "passive"))
      (node (ref "J1") (pin "19") (pinfunction "19_19") (pintype "bidirectional"))
    )
    (net (code "30") (name "Net-(EPD_C8-Pad2)") (class "Default")
      (node (ref "EPD_C8") (pin "2") (pinfunction "2_2") (pintype "passive"))
      (node (ref "J1") (pin "20") (pinfunction "20_20") (pintype "bidirectional"))
    )
    (net (code "31") (name "Net-(EPD_C10-Pad2)") (class "Default")
      (node (ref "EPD_C10") (pin "2") (pinfunction "2_2") (pintype "passive"))
      (node (ref "J1") (pin "22") (pinfunction "22_22") (pintype "bidirectional"))
    )
    (net (code "32") (name "Net-(EPD_C12-Pad2)") (class "Default")
      (node (ref "EPD_C12") (pin "2") (pinfunction "2_2") (pintype "passive"))
      (node (ref "J1") (pin "24") (pinfunction "24_24") (pintype "bidirectional"))
    )
    (net (code "33") (name "Net-(IC1-CT)") (class "Default")
      (node (ref "C_DELAY") (pin "1") (pinfunction "1_1") (pintype "passive"))
      (node (ref "IC1") (pin "5") (pinfunction "CT_5") (pintype "bidirectional"))
    )
    (net (code "34") (name "Net-(J2-PadA5)") (class "Default")
      (node (ref "J2") (pin "A5") (pinfunction "A5_A5") (pintype "bidirectional"))
      (node (ref "R2-USB1") (pin "2") (pinfunction "2_2") (pintype "passive"))
    )
    (net (code "35") (name "Net-(J2-PadB5)") (class "Default")
      (node (ref "J2") (pin "B5") (pinfunction "B5_B5") (pintype "bidirectional"))
      (node (ref "R2-USB") (pin "1") (pinfunction "1_1") (pintype "passive"))
    )
    (net (code "36") (name "Net-(U5-PROG)") (class "Default")
      (node (ref "R2_BAT") (pin "2") (pinfunction "2_2") (pintype "passive"))
      (node (ref "U5") (pin "5") (pinfunction "PROG_5") (pintype "input"))
    )
    (net (code "37") (name "Net-(U5-STAT)") (class "Default")
      (node (ref "R1_BAT") (pin "2") (pinfunction "2_2") (pintype "passive"))
      (node (ref "U5") (pin "1") (pinfunction "STAT_1") (pintype "output"))
    )
    (net (code "38") (name "PREVGH") (class "Default")
      (node (ref "D5") (pin "1") (pinfunction "K_1") (pintype "bidirectional"))
      (node (ref "EPD_C9") (pin "2") (pinfunction "2_2") (pintype "passive"))
      (node (ref "J1") (pin "21") (pinfunction "21_21") (pintype "bidirectional"))
    )
    (net (code "39") (name "PREVGL") (class "Default")
      (node (ref "D4") (pin "2") (pinfunction "A_2") (pintype "bidirectional"))
      (node (ref "EPD_C11") (pin "2") (pinfunction "2_2") (pintype "passive"))
      (node (ref "J1") (pin "23") (pinfunction "23_23") (pintype "bidirectional"))
    )
    (net (code "40") (name "RESE") (class "Default")
      (node (ref "J1") (pin "3") (pinfunction "3_3") (pintype "bidirectional"))
      (node (ref "Q3") (pin "2") (pinfunction "S_2") (pintype "bidirectional"))
      (node (ref "R3") (pin "2") (pinfunction "2_2") (pintype "passive"))
    )
    (net (code "41") (name "RESE'") (class "Default")
      (node (ref "R2") (pin "2") (pinfunction "2_2") (pintype "passive"))
      (node (ref "R3") (pin "1") (pinfunction "1_1") (pintype "passive"))
      (node (ref "SJ1") (pin "2") (pinfunction "2_2") (pintype "passive"))
    )
    (net (code "42") (name "RESET") (class "Default")
      (node (ref "C5") (pin "1") (pinfunction "1_1") (pintype "passive"))
      (node (ref "IC1") (pin "1") (pinfunction "VOUT_1") (pintype "bidirectional"))
      (node (ref "RESET_BUTTON") (pin "3") (pinfunction "3_3") (pintype "passive"))
      (node (ref "RESET_BUTTON") (pin "4") (pinfunction "4_4") (pintype "passive"))
      (node (ref "R_RESET") (pin "1") (pinfunction "1_1") (pintype "passive"))
      (node (ref "U2") (pin "3") (pinfunction "EN_3") (pintype "input"))
    )
    (net (code "43") (name "RTC_RST") (class "Default")
      (node (ref "U2") (pin "16") (pinfunction "IO18_16") (pintype "bidirectional"))
      (node (ref "U3") (pin "4") (pinfunction "~{RST}_4") (pintype "input"))
    )
    (net (code "44") (name "RX") (class "Default")
      (node (ref "RX") (pin "TP") (pinfunction "TP_TP") (pintype "input"))
      (node (ref "U2") (pin "24") (pinfunction "RXD0/GPIO17_24") (pintype "bidirectional"))
    )
    (net (code "45") (name "SCK") (class "Default")
      (node (ref "D10") (pin "2") (pinfunction "2_2") (pintype "passive"))
      (node (ref "J1") (pin "13") (pinfunction "13_13") (pintype "bidirectional"))
      (node (ref "J4") (pin "P5") (pinfunction "CLK_P5") (pintype "bidirectional"))
      (node (ref "R6") (pin "1") (pinfunction "1_1") (pintype "passive"))
      (node (ref "SCK") (pin "TP") (pinfunction "TP_TP") (pintype "input"))
      (node (ref "U1") (pin "6") (pinfunction "CLK_6") (pintype "input"))
      (node (ref "U2") (pin "6") (pinfunction "IO6_6") (pintype "bidirectional"))
    )
    (net (code "46") (name "SCL") (class "Default")
      (node (ref "J3") (pin "4") (pinfunction "4_4") (pintype "passive"))
      (node (ref "R2-PINH") (pin "1") (pinfunction "1_1") (pintype "passive"))
      (node (ref "SENSOR2") (pin "4") (pinfunction "SCK_4") (pintype "input"))
      (node (ref "U2") (pin "20") (pinfunction "IO22_20") (pintype "bidirectional"))
      (node (ref "U3") (pin "16") (pinfunction "SCL_16") (pintype "input"))
      (node (ref "U4") (pin "7") (pinfunction "SCL_7") (pintype "input"))
    )
    (net (code "47") (name "SDA") (class "Default")
      (node (ref "J3") (pin "3") (pinfunction "3_3") (pintype "passive"))
      (node (ref "R1_PINH") (pin "1") (pinfunction "1_1") (pintype "passive"))
      (node (ref "SENSOR2") (pin "3") (pinfunction "SDI_3") (pintype "bidirectional"))
      (node (ref "U2") (pin "19") (pinfunction "IO21_19") (pintype "bidirectional"))
      (node (ref "U3") (pin "15") (pinfunction "SDA_15") (pintype "bidirectional"))
      (node (ref "U4") (pin "8") (pinfunction "SDA_8") (pintype "bidirectional"))
    )
    (net (code "48") (name "SRC") (class "Default")
      (node (ref "C4") (pin "2") (pinfunction "2_2") (pintype "passive"))
      (node (ref "D5") (pin "2") (pinfunction "A_2") (pintype "bidirectional"))
      (node (ref "L1") (pin "1") (pinfunction "1_1") (pintype "passive"))
      (node (ref "Q3") (pin "3") (pinfunction "D_3") (pintype "bidirectional"))
    )
    (net (code "49") (name "SS_SD") (class "Default")
      (node (ref "D8") (pin "2") (pinfunction "2_2") (pintype "passive"))
      (node (ref "J4") (pin "P2") (pinfunction "CD/DAT3_P2") (pintype "bidirectional"))
      (node (ref "R10") (pin "1") (pinfunction "1_1") (pintype "passive"))
      (node (ref "U2") (pin "4") (pinfunction "IO4_4") (pintype "bidirectional"))
    )
    (net (code "50") (name "TX") (class "Default")
      (node (ref "TX") (pin "TP") (pinfunction "TP_TP") (pintype "input"))
      (node (ref "U2") (pin "25") (pinfunction "TXD0/GPIO16_25") (pintype "bidirectional"))
    )
    (net (code "51") (name "USB_D+") (class "Default")
      (node (ref "D1") (pin "1") (pinfunction "I/O1_1_1") (pintype "bidirectional"))
      (node (ref "U2") (pin "14") (pinfunction "IO13_14") (pintype "bidirectional"))
    )
    (net (code "52") (name "USB_D-") (class "Default")
      (node (ref "D1") (pin "3") (pinfunction "I/O2_1_3") (pintype "bidirectional"))
      (node (ref "U2") (pin "13") (pinfunction "IO12_13") (pintype "bidirectional"))
    )
    (net (code "53") (name "VBAT") (class "Default")
      (node (ref "C2_BAT") (pin "1") (pinfunction "1_1") (pintype "passive"))
      (node (ref "Q1") (pin "3") (pinfunction "D_3") (pintype "bidirectional"))
      (node (ref "U4") (pin "2") (pinfunction "CELL_2") (pintype "power_in"))
      (node (ref "U4") (pin "3") (pinfunction "VDD_3") (pintype "power_in"))
      (node (ref "U5") (pin "3") (pinfunction "VBAT_3") (pintype "power_in"))
      (node (ref "VBAT") (pin "TP") (pinfunction "TP_TP") (pintype "input"))
    )
    (net (code "54") (name "VBUS") (class "Default")
      (node (ref "C1_BAT") (pin "1") (pinfunction "1_1") (pintype "passive"))
      (node (ref "C4_USB") (pin "1") (pinfunction "1_1") (pintype "passive"))
      (node (ref "C5_USB") (pin "1") (pinfunction "1_1") (pintype "passive"))
      (node (ref "CHG_LED") (pin "A") (pinfunction "A_A") (pintype "passive"))
      (node (ref "D1") (pin "5") (pinfunction "VBUS_5") (pintype "bidirectional"))
      (node (ref "D2") (pin "2") (pinfunction "ANODE_2") (pintype "bidirectional"))
      (node (ref "PFMF.050.1") (pin "2") (pinfunction "2_2") (pintype "passive"))
      (node (ref "Q1") (pin "1") (pinfunction "G_1") (pintype "bidirectional"))
      (node (ref "R1_PWRUSB") (pin "2") (pinfunction "2_2") (pintype "passive"))
      (node (ref "TP14") (pin "TP") (pinfunction "TP_TP") (pintype "input"))
      (node (ref "U5") (pin "4") (pinfunction "VIN_4") (pintype "power_in"))
    )
    (net (code "55") (name "VRTC") (class "Default")
      (node (ref "C10_SUPERCAP") (pin "1") (pinfunction "1_1") (pintype "passive"))
      (node (ref "C8") (pin "1") (pinfunction "1_1") (pintype "passive"))
      (node (ref "R_CAPACITOR") (pin "2") (pinfunction "2_2") (pintype "passive"))
      (node (ref "U3") (pin "14") (pinfunction "VBAT_14") (pintype "power_in"))
    )
    (net (code "56") (name "VUSB") (class "Default")
      (node (ref "J2") (pin "A4") (pinfunction "A4_A4") (pintype "bidirectional"))
      (node (ref "J2") (pin "A9") (pinfunction "A9_A9") (pintype "bidirectional"))
      (node (ref "J2") (pin "B4") (pinfunction "B4_B4") (pintype "bidirectional"))
      (node (ref "J2") (pin "B9") (pinfunction "B9_B9") (pintype "bidirectional"))
      (node (ref "PFMF.050.1") (pin "1") (pinfunction "1_1") (pintype "passive"))
    )
    (net (code "57") (name "unconnected-(IC1-NC-Pad4)") (class "Default")
      (node (ref "IC1") (pin "4") (pinfunction "NC_4") (pintype "no_connect"))
    )
    (net (code "58") (name "unconnected-(IC4-NC-Pad4)") (class "Default")
      (node (ref "IC4") (pin "4") (pinfunction "NC_4") (pintype "no_connect"))
    )
    (net (code "59") (name "unconnected-(J1-Pad1)") (class "Default")
      (node (ref "J1") (pin "1") (pinfunction "1_1") (pintype "bidirectional"))
    )
    (net (code "60") (name "unconnected-(J1-Pad6)") (class "Default")
      (node (ref "J1") (pin "6") (pinfunction "6_6") (pintype "bidirectional"))
    )
    (net (code "61") (name "unconnected-(J1-Pad7)") (class "Default")
      (node (ref "J1") (pin "7") (pinfunction "7_7") (pintype "bidirectional"))
    )
    (net (code "62") (name "unconnected-(J2-PadA8)") (class "Default")
      (node (ref "J2") (pin "A8") (pinfunction "A8_A8") (pintype "bidirectional"))
    )
    (net (code "63") (name "unconnected-(J2-PadB8)") (class "Default")
      (node (ref "J2") (pin "B8") (pinfunction "B8_B8") (pintype "bidirectional"))
    )
    (net (code "64") (name "unconnected-(J4-DAT1-PadP8)") (class "Default")
      (node (ref "J4") (pin "P8") (pinfunction "DAT1_P8") (pintype "bidirectional"))
    )
    (net (code "65") (name "unconnected-(J4-DAT2-PadP1)") (class "Default")
      (node (ref "J4") (pin "P1") (pinfunction "DAT2_P1") (pintype "bidirectional"))
    )
    (net (code "66") (name "unconnected-(J4-DETECTION_1-PadS1)") (class "Default")
      (node (ref "J4") (pin "S1") (pinfunction "DETECTION_1_S1") (pintype "bidirectional"))
    )
    (net (code "67") (name "unconnected-(J4-DETECTION_2-PadS2)") (class "Default")
      (node (ref "J4") (pin "S2") (pinfunction "DETECTION_2_S2") (pintype "bidirectional"))
    )
    (net (code "68") (name "unconnected-(Q1-S-Pad2)") (class "Default")
      (node (ref "Q1") (pin "2") (pinfunction "S_2") (pintype "bidirectional"))
    )
    (net (code "69") (name "unconnected-(U1-DO(IO1)-Pad2)") (class "Default")
      (node (ref "U1") (pin "2") (pinfunction "DO(IO1)_2") (pintype "bidirectional"))
    )
    (net (code "70") (name "unconnected-(U2-NC-Pad22)") (class "Default")
      (node (ref "U2") (pin "22") (pinfunction "NC_22") (pintype "no_connect"))
    )
    (net (code "71") (name "unconnected-(U4-~{ALERT}-Pad5)") (class "Default")
      (node (ref "U4") (pin "5") (pinfunction "~{ALERT}_5") (pintype "output"))
    )
  )
)
